# ADC.net
KiCad netlist of a schematic drawn in Altium Designer
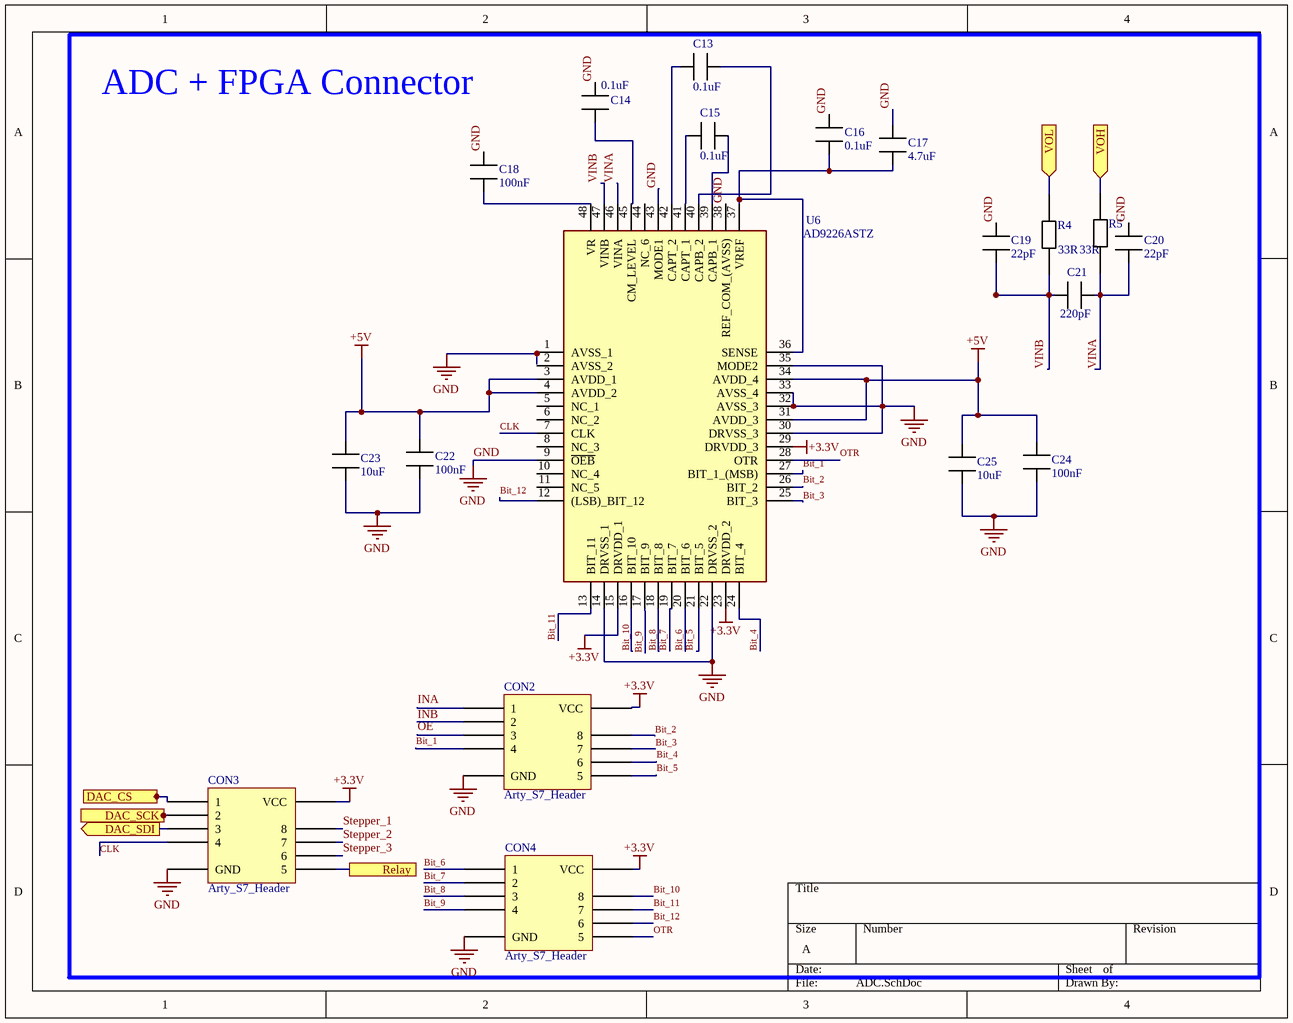
[diagram p0: ADC.SchDoc]

(export (version "E")
  (design (tool "Eeschema 10.0.6"))
  (components
    (comp (ref "C13")
      (value "0.1uF")
      (footprint "CAP_0805")
      (description "CAP_0805")
      (fields (field (name "VAL") "0.1uF"))
      (libsource (lib "Passives") (part "CAP_0805"))
    )
    (comp (ref "C14")
      (value "0.1uF")
      (footprint "CAP_0805")
      (description "CAP_0805")
      (fields (field (name "VAL") "0.1uF"))
      (libsource (lib "Passives") (part "CAP_0805"))
    )
    (comp (ref "C15")
      (value "0.1uF")
      (footprint "CAP_0805")
      (description "CAP_0805")
      (fields (field (name "VAL") "0.1uF"))
      (libsource (lib "Passives") (part "CAP_0805"))
    )
    (comp (ref "C16")
      (value "0.1uF")
      (footprint "CAP_0805")
      (description "CAP_0805")
      (fields (field (name "VAL") "0.1uF"))
      (libsource (lib "Passives") (part "CAP_0805"))
    )
    (comp (ref "C17")
      (value "4.7uF")
      (footprint "CAP_0805")
      (description "CAP_0805")
      (fields (field (name "VAL") "4.7uF"))
      (libsource (lib "Passives") (part "CAP_0805"))
    )
    (comp (ref "C18")
      (value "100nF")
      (footprint "CAP_0805")
      (description "CAP_0805")
      (fields (field (name "VAL") "100nF"))
      (libsource (lib "Passives") (part "CAP_0805"))
    )
    (comp (ref "C19")
      (value "22pF")
      (footprint "CAP_0805")
      (description "CAP_0805")
      (fields (field (name "VAL") "22pF"))
      (libsource (lib "Passives") (part "CAP_0805"))
    )
    (comp (ref "C20")
      (value "22pF")
      (footprint "CAP_0805")
      (description "CAP_0805")
      (fields (field (name "VAL") "22pF"))
      (libsource (lib "Passives") (part "CAP_0805"))
    )
    (comp (ref "C21")
      (value "220pF")
      (footprint "CAP_0805")
      (description "CAP_0805")
      (fields (field (name "VAL") "220pF"))
      (libsource (lib "Passives") (part "CAP_0805"))
    )
    (comp (ref "C22")
      (value "100nF")
      (footprint "CAP_0805")
      (description "CAP_0805")
      (fields (field (name "VAL") "100nF"))
      (libsource (lib "Passives") (part "CAP_0805"))
    )
    (comp (ref "C23")
      (value "10uF")
      (footprint "CAP_0805")
      (description "CAP_0805")
      (fields (field (name "VAL") "10uF"))
      (libsource (lib "Passives") (part "CAP_0805"))
    )
    (comp (ref "C24")
      (value "100nF")
      (footprint "CAP_0805")
      (description "CAP_0805")
      (fields (field (name "VAL") "100nF"))
      (libsource (lib "Passives") (part "CAP_0805"))
    )
    (comp (ref "C25")
      (value "10uF")
      (footprint "CAP_0805")
      (description "CAP_0805")
      (fields (field (name "VAL") "10uF"))
      (libsource (lib "Passives") (part "CAP_0805"))
    )
    (comp (ref "CON2")
      (value "Arty_S7_Header")
      (footprint "CON_2x6_2.54MM_THT")
      (libsource (lib "Connectors") (part "Arty_S7_Header"))
    )
    (comp (ref "CON3")
      (value "Arty_S7_Header")
      (footprint "CON_2x6_2.54MM_THT")
      (libsource (lib "Connectors") (part "Arty_S7_Header"))
    )
    (comp (ref "CON4")
      (value "Arty_S7_Header")
      (footprint "CON_2x6_2.54MM_THT")
      (libsource (lib "Connectors") (part "Arty_S7_Header"))
    )
    (comp (ref "R4")
      (value "33R")
      (footprint "RES_0805")
      (description "RES_0805")
      (fields (field (name "VAL") "33R"))
      (libsource (lib "Passives") (part "RES_0805"))
    )
    (comp (ref "R5")
      (value "33R")
      (footprint "RES_0805")
      (description "RES_0805")
      (fields (field (name "VAL") "33R"))
      (libsource (lib "Passives") (part "RES_0805"))
    )
    (comp (ref "U6")
      (value "AD9226ASTZ")
      (footprint "QFP50P900X900X160-48N")
      (description "AD9226ASTZ, 12 bit-Bit DAC 65Msps, Parallel, 48-Pin LQFP")
      (fields (field (name "MOUSER PART NUMBER") "584-AD9226ASTZ"))
      (libsource (lib "IC_Digital") (part "AD9226ASTZ"))
    )
  )
  (nets
    (net (code "1") (name "+3.3V") (class "Default")
      (node (ref "CON2") (pin "6") (pinfunction "VCC_6") (pintype "power_in"))
      (node (ref "CON3") (pin "6") (pinfunction "VCC_6") (pintype "power_in"))
      (node (ref "CON4") (pin "6") (pinfunction "VCC_6") (pintype "power_in"))
      (node (ref "U6") (pin "15") (pinfunction "DRVDD_1_15") (pintype "passive"))
      (node (ref "U6") (pin "23") (pinfunction "DRVDD_2_23") (pintype "passive"))
      (node (ref "U6") (pin "29") (pinfunction "DRVDD_3_29") (pintype "passive"))
    )
    (net (code "2") (name "+5V") (class "Default")
      (node (ref "C22") (pin "1") (pinfunction "1_1") (pintype "passive"))
      (node (ref "C23") (pin "2") (pinfunction "2_2") (pintype "passive"))
      (node (ref "C24") (pin "1") (pinfunction "1_1") (pintype "passive"))
      (node (ref "C25") (pin "2") (pinfunction "2_2") (pintype "passive"))
      (node (ref "U6") (pin "3") (pinfunction "AVDD_1_3") (pintype "passive"))
      (node (ref "U6") (pin "31") (pinfunction "AVDD_3_31") (pintype "passive"))
      (node (ref "U6") (pin "34") (pinfunction "AVDD_4_34") (pintype "passive"))
      (node (ref "U6") (pin "4") (pinfunction "AVDD_2_4") (pintype "passive"))
    )
    (net (code "3") (name "/Bit_1") (class "Default")
      (node (ref "CON2") (pin "4") (pinfunction "4_4") (pintype "passive"))
      (node (ref "U6") (pin "27") (pinfunction "BIT_1_(MSB)_27") (pintype "passive"))
    )
    (net (code "4") (name "/Bit_2") (class "Default")
      (node (ref "CON2") (pin "10") (pinfunction "8_10") (pintype "passive"))
      (node (ref "U6") (pin "26") (pinfunction "BIT_2_26") (pintype "passive"))
    )
    (net (code "5") (name "/Bit_3") (class "Default")
      (node (ref "CON2") (pin "9") (pinfunction "7_9") (pintype "passive"))
      (node (ref "U6") (pin "25") (pinfunction "BIT_3_25") (pintype "passive"))
    )
    (net (code "6") (name "/Bit_4") (class "Default")
      (node (ref "CON2") (pin "8") (pinfunction "6_8") (pintype "passive"))
      (node (ref "U6") (pin "24") (pinfunction "BIT_4_24") (pintype "passive"))
    )
    (net (code "7") (name "/Bit_5") (class "Default")
      (node (ref "CON2") (pin "7") (pinfunction "5_7") (pintype "passive"))
      (node (ref "U6") (pin "21") (pinfunction "BIT_5_21") (pintype "passive"))
    )
    (net (code "8") (name "/Bit_6") (class "Default")
      (node (ref "CON4") (pin "1") (pinfunction "1_1") (pintype "passive"))
      (node (ref "U6") (pin "20") (pinfunction "BIT_6_20") (pintype "passive"))
    )
    (net (code "9") (name "/Bit_7") (class "Default")
      (node (ref "CON4") (pin "2") (pinfunction "2_2") (pintype "passive"))
      (node (ref "U6") (pin "19") (pinfunction "BIT_7_19") (pintype "passive"))
    )
    (net (code "10") (name "/Bit_8") (class "Default")
      (node (ref "CON4") (pin "3") (pinfunction "3_3") (pintype "passive"))
      (node (ref "U6") (pin "18") (pinfunction "BIT_8_18") (pintype "passive"))
    )
    (net (code "11") (name "/Bit_9") (class "Default")
      (node (ref "CON4") (pin "4") (pinfunction "4_4") (pintype "passive"))
      (node (ref "U6") (pin "17") (pinfunction "BIT_9_17") (pintype "passive"))
    )
    (net (code "12") (name "/Bit_10") (class "Default")
      (node (ref "CON4") (pin "10") (pinfunction "8_10") (pintype "passive"))
      (node (ref "U6") (pin "16") (pinfunction "BIT_10_16") (pintype "passive"))
    )
    (net (code "13") (name "/Bit_11") (class "Default")
      (node (ref "CON4") (pin "9") (pinfunction "7_9") (pintype "passive"))
      (node (ref "U6") (pin "13") (pinfunction "BIT_11_13") (pintype "passive"))
    )
    (net (code "14") (name "/Bit_12") (class "Default")
      (node (ref "CON4") (pin "8") (pinfunction "6_8") (pintype "passive"))
      (node (ref "U6") (pin "12") (pinfunction "(LSB)_BIT_12_12") (pintype "passive"))
    )
    (net (code "15") (name "/CLK") (class "Default")
      (node (ref "CON3") (pin "4") (pinfunction "4_4") (pintype "passive"))
      (node (ref "U6") (pin "7") (pinfunction "CLK_7") (pintype "passive"))
    )
    (net (code "16") (name "/DAC_CS") (class "Default")
      (node (ref "CON3") (pin "1") (pinfunction "1_1") (pintype "passive"))
    )
    (net (code "17") (name "/DAC_SCK") (class "Default")
      (node (ref "CON3") (pin "2") (pinfunction "2_2") (pintype "passive"))
    )
    (net (code "18") (name "/DAC_SDI") (class "Default")
      (node (ref "CON3") (pin "3") (pinfunction "3_3") (pintype "passive"))
    )
    (net (code "19") (name "/INA") (class "Default")
      (node (ref "CON2") (pin "1") (pinfunction "1_1") (pintype "passive"))
    )
    (net (code "20") (name "/INB") (class "Default")
      (node (ref "CON2") (pin "2") (pinfunction "2_2") (pintype "passive"))
    )
    (net (code "21") (name "/OE") (class "Default")
      (node (ref "CON2") (pin "3") (pinfunction "3_3") (pintype "passive"))
    )
    (net (code "22") (name "/OTR") (class "Default")
      (node (ref "CON4") (pin "7") (pinfunction "5_7") (pintype "passive"))
      (node (ref "U6") (pin "28") (pinfunction "OTR_28") (pintype "passive"))
    )
    (net (code "23") (name "/Relay") (class "Default")
      (node (ref "CON3") (pin "7") (pinfunction "5_7") (pintype "passive"))
    )
    (net (code "24") (name "/Stepper_1") (class "Default")
      (node (ref "CON3") (pin "10") (pinfunction "8_10") (pintype "passive"))
    )
    (net (code "25") (name "/Stepper_2") (class "Default")
      (node (ref "CON3") (pin "9") (pinfunction "7_9") (pintype "passive"))
    )
    (net (code "26") (name "/Stepper_3") (class "Default")
      (node (ref "CON3") (pin "8") (pinfunction "6_8") (pintype "passive"))
    )
    (net (code "27") (name "/VINA") (class "Default")
      (node (ref "C20") (pin "2") (pinfunction "2_2") (pintype "passive"))
      (node (ref "C21") (pin "2") (pinfunction "2_2") (pintype "passive"))
      (node (ref "R5") (pin "1") (pinfunction "1_1") (pintype "passive"))
      (node (ref "U6") (pin "46") (pinfunction "VINA_46") (pintype "passive"))
    )
    (net (code "28") (name "/VINB") (class "Default")
      (node (ref "C19") (pin "2") (pinfunction "2_2") (pintype "passive"))
      (node (ref "C21") (pin "1") (pinfunction "1_1") (pintype "passive"))
      (node (ref "R4") (pin "1") (pinfunction "1_1") (pintype "passive"))
      (node (ref "U6") (pin "47") (pinfunction "VINB_47") (pintype "passive"))
    )
    (net (code "29") (name "/VOH") (class "Default")
      (node (ref "R5") (pin "2") (pinfunction "2_2") (pintype "passive"))
    )
    (net (code "30") (name "/VOL") (class "Default")
      (node (ref "R4") (pin "2") (pinfunction "2_2") (pintype "passive"))
    )
    (net (code "31") (name "GND") (class "Default")
      (node (ref "C14") (pin "1") (pinfunction "1_1") (pintype "passive"))
      (node (ref "C16") (pin "1") (pinfunction "1_1") (pintype "passive"))
      (node (ref "C17") (pin "1") (pinfunction "1_1") (pintype "passive"))
      (node (ref "C18") (pin "1") (pinfunction "1_1") (pintype "passive"))
      (node (ref "C19") (pin "1") (pinfunction "1_1") (pintype "passive"))
      (node (ref "C20") (pin "1") (pinfunction "1_1") (pintype "passive"))
      (node (ref "C22") (pin "2") (pinfunction "2_2") (pintype "passive"))
      (node (ref "C23") (pin "1") (pinfunction "1_1") (pintype "passive"))
      (node (ref "C24") (pin "2") (pinfunction "2_2") (pintype "passive"))
      (node (ref "C25") (pin "1") (pinfunction "1_1") (pintype "passive"))
      (node (ref "CON2") (pin "5") (pinfunction "GND_5") (pintype "power_in"))
      (node (ref "CON3") (pin "5") (pinfunction "GND_5") (pintype "power_in"))
      (node (ref "CON4") (pin "5") (pinfunction "GND_5") (pintype "power_in"))
      (node (ref "U6") (pin "1") (pinfunction "AVSS_1_1") (pintype "passive"))
      (node (ref "U6") (pin "14") (pinfunction "DRVSS_1_14") (pintype "passive"))
      (node (ref "U6") (pin "22") (pinfunction "DRVSS_2_22") (pintype "passive"))
      (node (ref "U6") (pin "30") (pinfunction "DRVSS_3_30") (pintype "passive"))
      (node (ref "U6") (pin "32") (pinfunction "AVSS_3_32") (pintype "passive"))
      (node (ref "U6") (pin "33") (pinfunction "AVSS_4_33") (pintype "passive"))
      (node (ref "U6") (pin "35") (pinfunction "MODE2_35") (pintype "passive"))
      (node (ref "U6") (pin "38") (pinfunction "REF_COM_(AVSS)_38") (pintype "passive"))
      (node (ref "U6") (pin "43") (pinfunction "MODE1_43") (pintype "passive"))
      (node (ref "U6") (pin "9") (pinfunction "~{OEB}_9") (pintype "passive"))
    )
    (net (code "32") (name "Net-(U6-CAPB_1)") (class "Default")
      (node (ref "C15") (pin "2") (pinfunction "2_2") (pintype "passive"))
      (node (ref "U6") (pin "39") (pinfunction "CAPB_1_39") (pintype "passive"))
    )
    (net (code "33") (name "Net-(U6-CAPB_2)") (class "Default")
      (node (ref "C13") (pin "2") (pinfunction "2_2") (pintype "passive"))
      (node (ref "U6") (pin "40") (pinfunction "CAPB_2_40") (pintype "passive"))
    )
    (net (code "34") (name "Net-(U6-CAPT_1)") (class "Default")
      (node (ref "C15") (pin "1") (pinfunction "1_1") (pintype "passive"))
      (node (ref "U6") (pin "41") (pinfunction "CAPT_1_41") (pintype "passive"))
    )
    (net (code "35") (name "Net-(U6-CAPT_2)") (class "Default")
      (node (ref "C13") (pin "1") (pinfunction "1_1") (pintype "passive"))
      (node (ref "U6") (pin "42") (pinfunction "CAPT_2_42") (pintype "passive"))
    )
    (net (code "36") (name "Net-(U6-CM_LEVEL)") (class "Default")
      (node (ref "C14") (pin "2") (pinfunction "2_2") (pintype "passive"))
      (node (ref "U6") (pin "45") (pinfunction "CM_LEVEL_45") (pintype "passive"))
    )
    (net (code "37") (name "Net-(U6-SENSE)") (class "Default")
      (node (ref "C16") (pin "2") (pinfunction "2_2") (pintype "passive"))
      (node (ref "C17") (pin "2") (pinfunction "2_2") (pintype "passive"))
      (node (ref "U6") (pin "36") (pinfunction "SENSE_36") (pintype "passive"))
      (node (ref "U6") (pin "37") (pinfunction "VREF_37") (pintype "passive"))
    )
    (net (code "38") (name "Net-(U6-VR)") (class "Default")
      (node (ref "C18") (pin "2") (pinfunction "2_2") (pintype "passive"))
      (node (ref "U6") (pin "48") (pinfunction "VR_48") (pintype "passive"))
    )
    (net (code "39") (name "unconnected-(U6-AVSS_2-Pad2)") (class "Default")
      (node (ref "U6") (pin "2") (pinfunction "AVSS_2_2") (pintype "passive"))
    )
    (net (code "40") (name "unconnected-(U6-NC_1-Pad5)") (class "Default")
      (node (ref "U6") (pin "5") (pinfunction "NC_1_5") (pintype "passive"))
    )
    (net (code "41") (name "unconnected-(U6-NC_2-Pad6)") (class "Default")
      (node (ref "U6") (pin "6") (pinfunction "NC_2_6") (pintype "passive"))
    )
    (net (code "42") (name "unconnected-(U6-NC_3-Pad8)") (class "Default")
      (node (ref "U6") (pin "8") (pinfunction "NC_3_8") (pintype "passive"))
    )
    (net (code "43") (name "unconnected-(U6-NC_4-Pad10)") (class "Default")
      (node (ref "U6") (pin "10") (pinfunction "NC_4_10") (pintype "passive"))
    )
    (net (code "44") (name "unconnected-(U6-NC_5-Pad11)") (class "Default")
      (node (ref "U6") (pin "11") (pinfunction "NC_5_11") (pintype "passive"))
    )
    (net (code "45") (name "unconnected-(U6-NC_6-Pad44)") (class "Default")
      (node (ref "U6") (pin "44") (pinfunction "NC_6_44") (pintype "passive"))
    )
  )
)
